# Schaltplan_Vier-Gewinnt_V2.net
KiCad netlist of a schematic drawn in EasyEDA
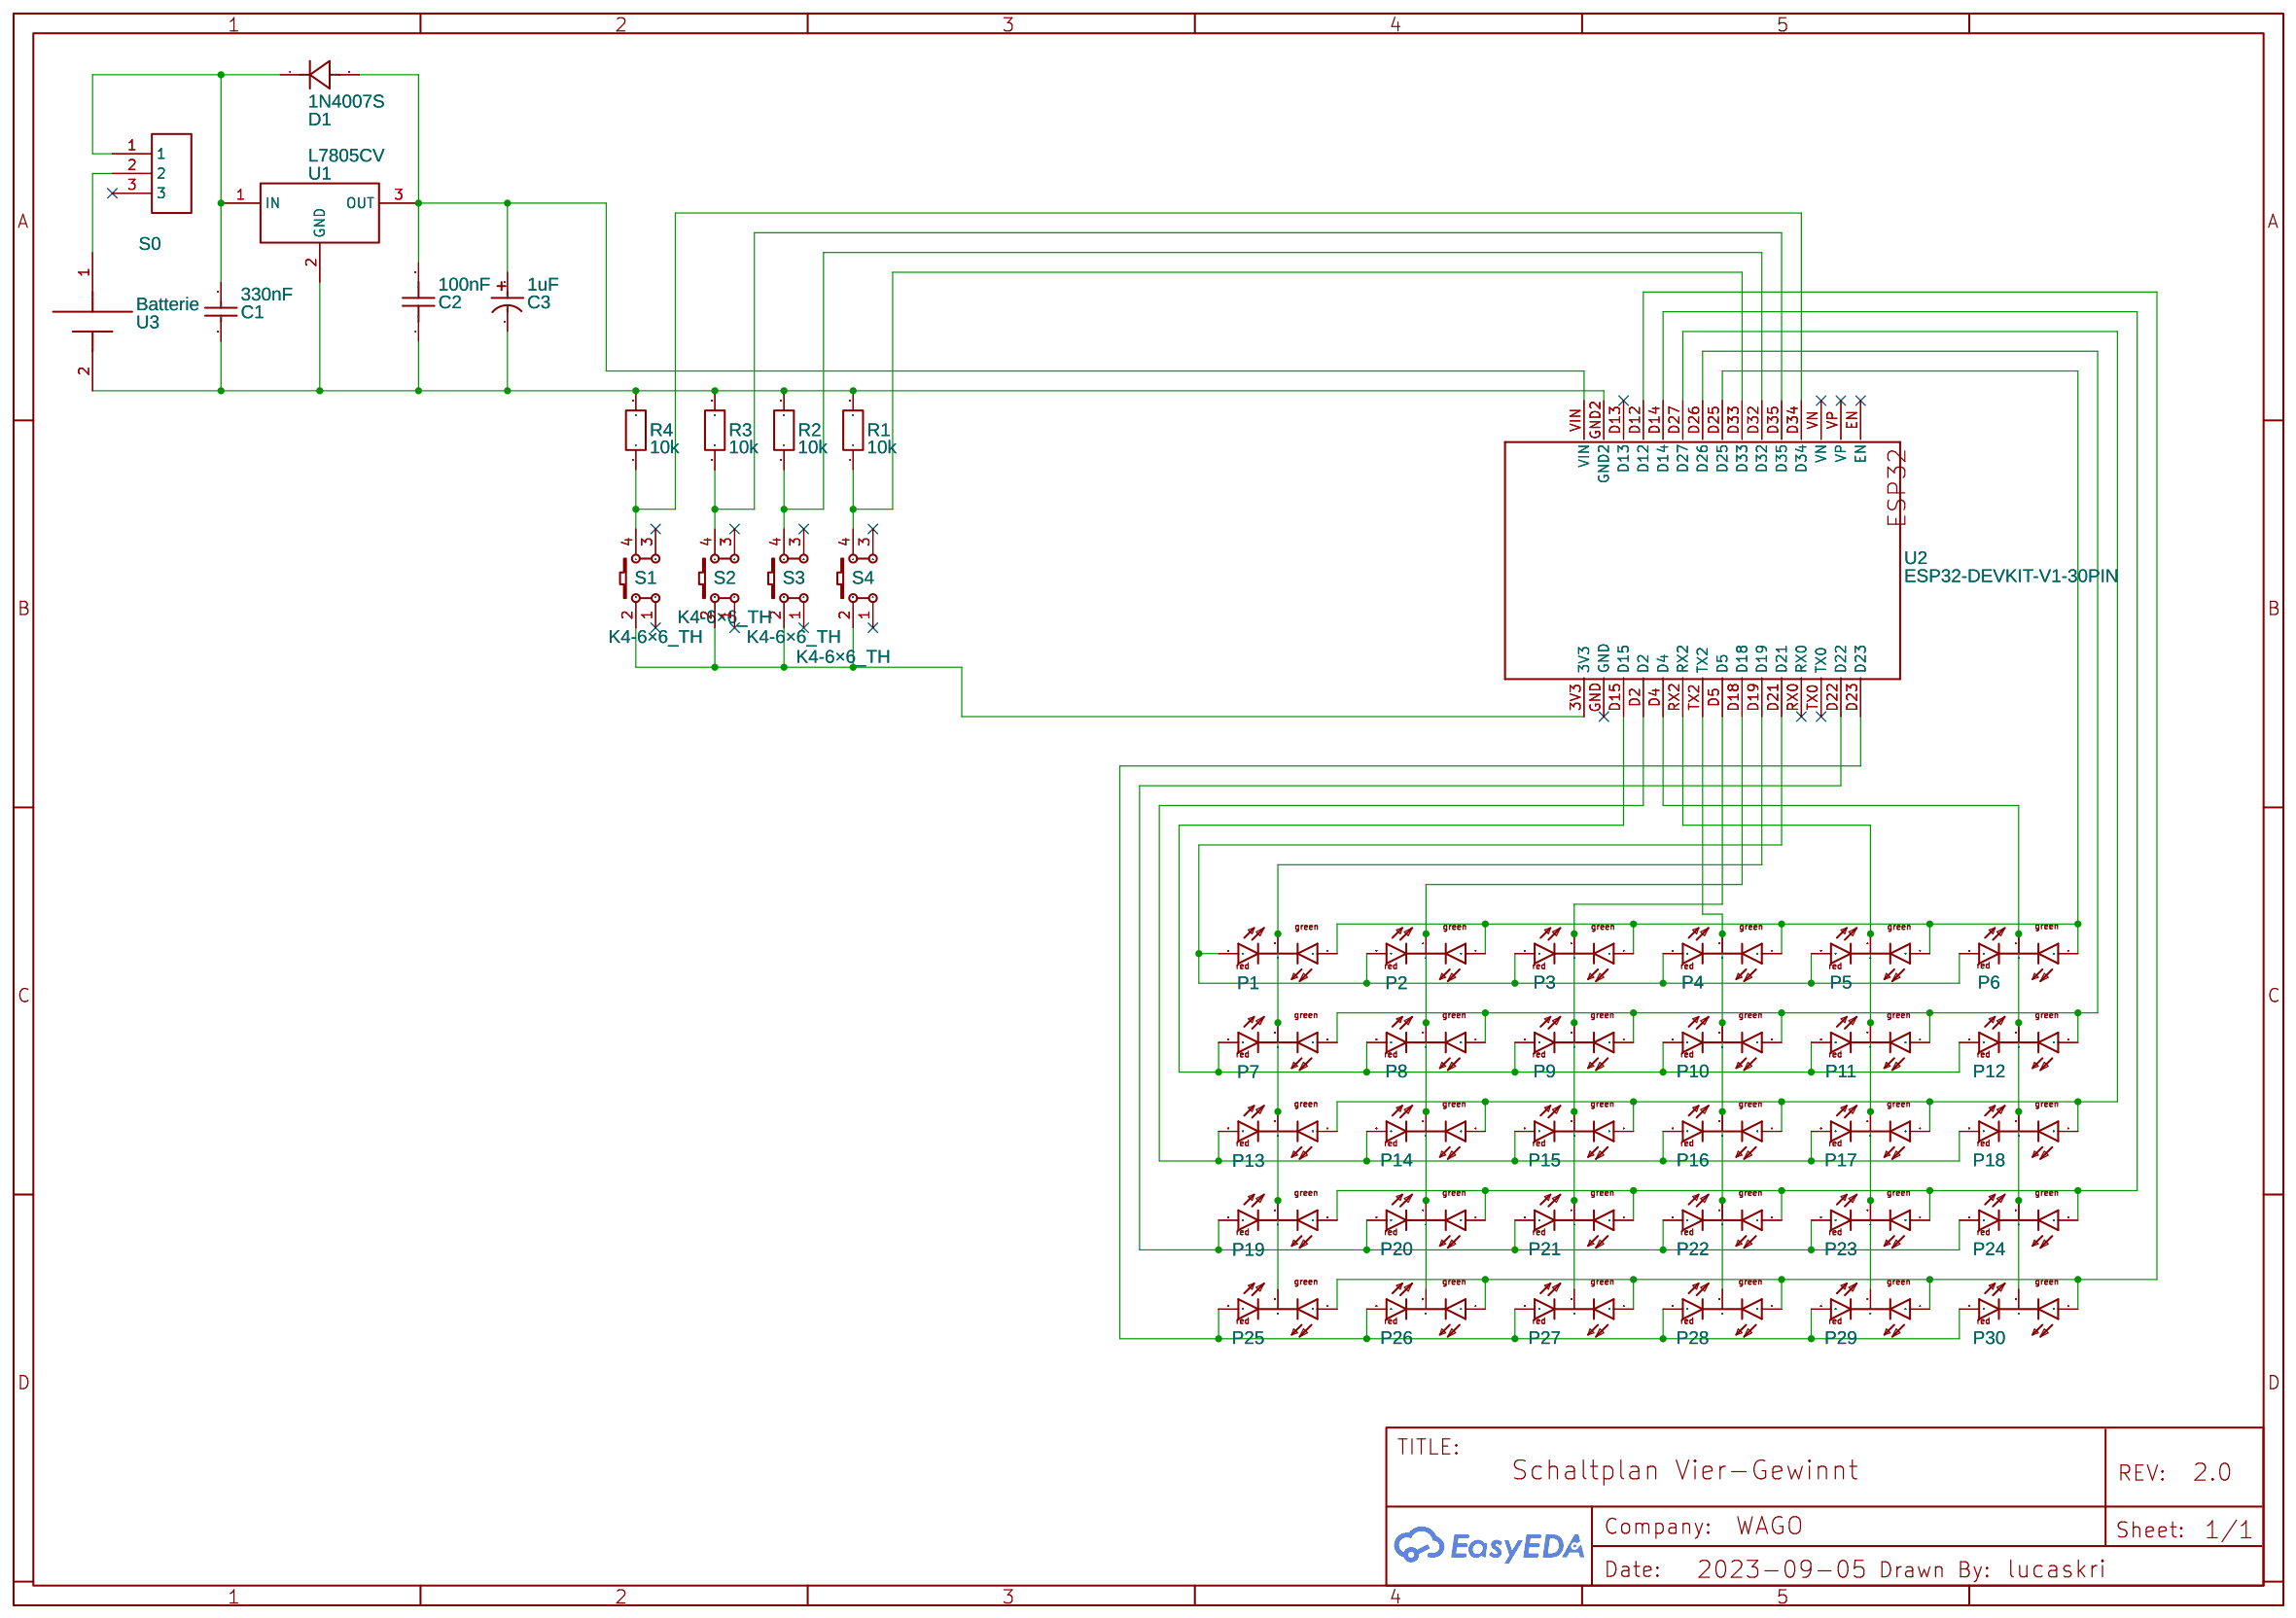
[diagram p0: schematic sheet]

(export (version "E")
  (design (tool "Eeschema 10.0.6"))
  (components
    (comp (ref "C1")
      (value "330nF")
      (fields (field (name "Manufacturer Part") "CT4-1206Y334M500PF3") (field (name "Manufacturer") "FH(风华)"))
      (libsource (lib "") (part "CT4-1206Y334M500PF3"))
    )
    (comp (ref "C2")
      (value "100nF")
      (fields (field (name "Manufacturer Part") "B32529C0104M289") (field (name "Manufacturer") "TDK"))
      (libsource (lib "") (part "B32529C0104M289"))
    )
    (comp (ref "C3")
      (value "1uF")
      (fields
        (field (name "Manufacturer Part") "KF105M050C05RR0VH2FP0")
        (field (name "Manufacturer") "CX(承兴)")
      )
      (libsource (lib "") (part "1uF 50V 4*5"))
    )
    (comp (ref "D1")
      (value "1N4007S")
      (fields (field (name "Manufacturer") "星海"))
      (libsource (lib "") (part "1N4007S"))
    )
    (comp (ref "P1") (value "NO") (libsource (lib "") (part "DUOLED-RG-C_1")))
    (comp (ref "P2") (value "NO") (libsource (lib "") (part "DUOLED-RG-C_1")))
    (comp (ref "P3") (value "NO") (libsource (lib "") (part "DUOLED-RG-C_1")))
    (comp (ref "P4") (value "NO") (libsource (lib "") (part "DUOLED-RG-C_1")))
    (comp (ref "P5") (value "NO") (libsource (lib "") (part "DUOLED-RG-C_1")))
    (comp (ref "P6") (value "NO") (libsource (lib "") (part "DUOLED-RG-C")))
    (comp (ref "P7") (value "NO") (libsource (lib "") (part "DUOLED-RG-C")))
    (comp (ref "P8") (value "NO") (libsource (lib "") (part "DUOLED-RG-C")))
    (comp (ref "P9") (value "NO") (libsource (lib "") (part "DUOLED-RG-C")))
    (comp (ref "P10") (value "NO") (libsource (lib "") (part "DUOLED-RG-C")))
    (comp (ref "P11") (value "NO") (libsource (lib "") (part "DUOLED-RG-C")))
    (comp (ref "P12") (value "NO") (libsource (lib "") (part "DUOLED-RG-C")))
    (comp (ref "P13") (value "NO") (libsource (lib "") (part "DUOLED-RG-C")))
    (comp (ref "P14") (value "NO") (libsource (lib "") (part "DUOLED-RG-C")))
    (comp (ref "P15") (value "NO") (libsource (lib "") (part "DUOLED-RG-C")))
    (comp (ref "P16") (value "NO") (libsource (lib "") (part "DUOLED-RG-C")))
    (comp (ref "P17") (value "NO") (libsource (lib "") (part "DUOLED-RG-C")))
    (comp (ref "P18") (value "NO") (libsource (lib "") (part "DUOLED-RG-C")))
    (comp (ref "P19") (value "NO") (libsource (lib "") (part "DUOLED-RG-C")))
    (comp (ref "P20") (value "NO") (libsource (lib "") (part "DUOLED-RG-C")))
    (comp (ref "P21") (value "NO") (libsource (lib "") (part "DUOLED-RG-C")))
    (comp (ref "P22") (value "NO") (libsource (lib "") (part "DUOLED-RG-C")))
    (comp (ref "P23") (value "NO") (libsource (lib "") (part "DUOLED-RG-C")))
    (comp (ref "P24") (value "NO") (libsource (lib "") (part "DUOLED-RG-C")))
    (comp (ref "P25") (value "NO") (libsource (lib "") (part "DUOLED-RG-C")))
    (comp (ref "P26") (value "NO") (libsource (lib "") (part "DUOLED-RG-C")))
    (comp (ref "P27") (value "NO") (libsource (lib "") (part "DUOLED-RG-C")))
    (comp (ref "P28") (value "NO") (libsource (lib "") (part "DUOLED-RG-C")))
    (comp (ref "P29") (value "NO") (libsource (lib "") (part "DUOLED-RG-C")))
    (comp (ref "P30") (value "NO") (libsource (lib "") (part "DUOLED-RG-C")))
    (comp (ref "R1") (value "10k") (libsource (lib "") (part "R_AXIAL-0.3_EU")))
    (comp (ref "R2") (value "10k") (libsource (lib "") (part "R_AXIAL-0.3_EU")))
    (comp (ref "R3") (value "10k") (libsource (lib "") (part "R_AXIAL-0.3_EU")))
    (comp (ref "R4") (value "10k") (libsource (lib "") (part "R_AXIAL-0.3_EU")))
    (comp (ref "S0") (value "NO") (libsource (lib "") (part "CSS-1201")))
    (comp (ref "S1")
      (value "K4-6×6_TH")
      (fields (field (name "Manufacturer Part") "K2-1102DP-E4SW-04") (field (name "Manufacturer") "韩国韩荣"))
      (libsource (lib "") (part "K4-6×6_TH"))
    )
    (comp (ref "S2")
      (value "K4-6×6_TH")
      (fields (field (name "Manufacturer Part") "K2-1102DP-E4SW-04") (field (name "Manufacturer") "韩国韩荣"))
      (libsource (lib "") (part "K4-6×6_TH"))
    )
    (comp (ref "S3")
      (value "K4-6×6_TH")
      (fields (field (name "Manufacturer Part") "K2-1102DP-E4SW-04") (field (name "Manufacturer") "韩国韩荣"))
      (libsource (lib "") (part "K4-6×6_TH"))
    )
    (comp (ref "S4")
      (value "K4-6×6_TH")
      (fields (field (name "Manufacturer Part") "K2-1102DP-E4SW-04") (field (name "Manufacturer") "韩国韩荣"))
      (libsource (lib "") (part "K4-6×6_TH"))
    )
    (comp (ref "U1")
      (value "L7805CV")
      (fields (field (name "Manufacturer") "STMicroelectronics"))
      (libsource (lib "") (part "L7805CV"))
    )
    (comp (ref "U2") (value "ESP32-DEVKIT-V1-30PIN") (libsource (lib "") (part "ESP32-DEVKIT-V1-30PIN")))
    (comp (ref "U3") (value "Batterie") (libsource (lib "") (part "Batterie")))
  )
  (nets
    (net (code "1") (name "Net-(D1-A)") (class "Default")
      (node (ref "C2") (pin "2") (pinfunction "2_2") (pintype "unspecified"))
      (node (ref "C3") (pin "1") (pinfunction "1_1") (pintype "input"))
      (node (ref "D1") (pin "2") (pinfunction "A_2") (pintype "unspecified"))
      (node (ref "U1") (pin "3") (pinfunction "OUT_3") (pintype "unspecified"))
      (node (ref "U2") (pin "VIN") (pinfunction "VIN_VIN") (pintype "unspecified"))
    )
    (net (code "2") (name "Net-(D1-K)") (class "Default")
      (node (ref "C1") (pin "2") (pinfunction "2_2") (pintype "input"))
      (node (ref "D1") (pin "1") (pinfunction "K_1") (pintype "unspecified"))
      (node (ref "S0") (pin "1") (pinfunction "1_1") (pintype "unspecified"))
      (node (ref "U1") (pin "1") (pinfunction "IN_1") (pintype "unspecified"))
    )
    (net (code "3") (name "Net-(P1-AG)") (class "Default")
      (node (ref "P1") (pin "AX") (pinfunction "AG_AX") (pintype "bidirectional"))
      (node (ref "P2") (pin "AX") (pinfunction "AG_AX") (pintype "bidirectional"))
      (node (ref "P3") (pin "AX") (pinfunction "AG_AX") (pintype "bidirectional"))
      (node (ref "P4") (pin "AX") (pinfunction "AG_AX") (pintype "bidirectional"))
      (node (ref "P5") (pin "AX") (pinfunction "AG_AX") (pintype "bidirectional"))
      (node (ref "P6") (pin "AX") (pinfunction "AG_AX") (pintype "bidirectional"))
      (node (ref "U2") (pin "D25") (pinfunction "D25_D25") (pintype "unspecified"))
    )
    (net (code "4") (name "Net-(P1-PadAR)") (class "Default")
      (node (ref "P1") (pin "AR") (pinfunction "AR_AR") (pintype "bidirectional"))
      (node (ref "P2") (pin "AR") (pinfunction "AR_AR") (pintype "bidirectional"))
      (node (ref "P3") (pin "AR") (pinfunction "AR_AR") (pintype "bidirectional"))
      (node (ref "P4") (pin "AR") (pinfunction "AR_AR") (pintype "bidirectional"))
      (node (ref "P5") (pin "AR") (pinfunction "AR_AR") (pintype "bidirectional"))
      (node (ref "P6") (pin "AR") (pinfunction "AR_AR") (pintype "bidirectional"))
      (node (ref "U2") (pin "D21") (pinfunction "D21_D21") (pintype "unspecified"))
    )
    (net (code "5") (name "Net-(P1-PadC)") (class "Default")
      (node (ref "P1") (pin "C") (pinfunction "C_C") (pintype "bidirectional"))
      (node (ref "P13") (pin "C") (pinfunction "C_C") (pintype "bidirectional"))
      (node (ref "P19") (pin "C") (pinfunction "C_C") (pintype "bidirectional"))
      (node (ref "P25") (pin "C") (pinfunction "C_C") (pintype "bidirectional"))
      (node (ref "P7") (pin "C") (pinfunction "C_C") (pintype "bidirectional"))
      (node (ref "U2") (pin "D19") (pinfunction "D19_D19") (pintype "unspecified"))
    )
    (net (code "6") (name "Net-(P10-AG)") (class "Default")
      (node (ref "P10") (pin "AX") (pinfunction "AG_AX") (pintype "bidirectional"))
      (node (ref "P11") (pin "AX") (pinfunction "AG_AX") (pintype "bidirectional"))
      (node (ref "P12") (pin "AX") (pinfunction "AG_AX") (pintype "bidirectional"))
      (node (ref "P7") (pin "AX") (pinfunction "AG_AX") (pintype "bidirectional"))
      (node (ref "P8") (pin "AX") (pinfunction "AG_AX") (pintype "bidirectional"))
      (node (ref "P9") (pin "AX") (pinfunction "AG_AX") (pintype "bidirectional"))
      (node (ref "U2") (pin "D26") (pinfunction "D26_D26") (pintype "unspecified"))
    )
    (net (code "7") (name "Net-(P10-PadAR)") (class "Default")
      (node (ref "P10") (pin "AR") (pinfunction "AR_AR") (pintype "bidirectional"))
      (node (ref "P11") (pin "AR") (pinfunction "AR_AR") (pintype "bidirectional"))
      (node (ref "P12") (pin "AR") (pinfunction "AR_AR") (pintype "bidirectional"))
      (node (ref "P7") (pin "AR") (pinfunction "AR_AR") (pintype "bidirectional"))
      (node (ref "P8") (pin "AR") (pinfunction "AR_AR") (pintype "bidirectional"))
      (node (ref "P9") (pin "AR") (pinfunction "AR_AR") (pintype "bidirectional"))
      (node (ref "U2") (pin "D15") (pinfunction "D15_D15") (pintype "unspecified"))
    )
    (net (code "8") (name "Net-(P10-PadC)") (class "Default")
      (node (ref "P10") (pin "C") (pinfunction "C_C") (pintype "bidirectional"))
      (node (ref "P16") (pin "C") (pinfunction "C_C") (pintype "bidirectional"))
      (node (ref "P22") (pin "C") (pinfunction "C_C") (pintype "bidirectional"))
      (node (ref "P28") (pin "C") (pinfunction "C_C") (pintype "bidirectional"))
      (node (ref "P4") (pin "C") (pinfunction "C_C") (pintype "bidirectional"))
      (node (ref "U2") (pin "TX2") (pinfunction "TX2_TX2") (pintype "unspecified"))
    )
    (net (code "9") (name "Net-(P11-PadC)") (class "Default")
      (node (ref "P11") (pin "C") (pinfunction "C_C") (pintype "bidirectional"))
      (node (ref "P17") (pin "C") (pinfunction "C_C") (pintype "bidirectional"))
      (node (ref "P23") (pin "C") (pinfunction "C_C") (pintype "bidirectional"))
      (node (ref "P29") (pin "C") (pinfunction "C_C") (pintype "bidirectional"))
      (node (ref "P5") (pin "C") (pinfunction "C_C") (pintype "bidirectional"))
      (node (ref "U2") (pin "RX2") (pinfunction "RX2_RX2") (pintype "unspecified"))
    )
    (net (code "10") (name "Net-(P12-PadC)") (class "Default")
      (node (ref "P12") (pin "C") (pinfunction "C_C") (pintype "bidirectional"))
      (node (ref "P18") (pin "C") (pinfunction "C_C") (pintype "bidirectional"))
      (node (ref "P24") (pin "C") (pinfunction "C_C") (pintype "bidirectional"))
      (node (ref "P30") (pin "C") (pinfunction "C_C") (pintype "bidirectional"))
      (node (ref "P6") (pin "C") (pinfunction "C_C") (pintype "bidirectional"))
      (node (ref "U2") (pin "D4") (pinfunction "D4_D4") (pintype "unspecified"))
    )
    (net (code "11") (name "Net-(P13-AG)") (class "Default")
      (node (ref "P13") (pin "AX") (pinfunction "AG_AX") (pintype "bidirectional"))
      (node (ref "P14") (pin "AX") (pinfunction "AG_AX") (pintype "bidirectional"))
      (node (ref "P15") (pin "AX") (pinfunction "AG_AX") (pintype "bidirectional"))
      (node (ref "P16") (pin "AX") (pinfunction "AG_AX") (pintype "bidirectional"))
      (node (ref "P17") (pin "AX") (pinfunction "AG_AX") (pintype "bidirectional"))
      (node (ref "P18") (pin "AX") (pinfunction "AG_AX") (pintype "bidirectional"))
      (node (ref "U2") (pin "D27") (pinfunction "D27_D27") (pintype "unspecified"))
    )
    (net (code "12") (name "Net-(P13-PadAR)") (class "Default")
      (node (ref "P13") (pin "AR") (pinfunction "AR_AR") (pintype "bidirectional"))
      (node (ref "P14") (pin "AR") (pinfunction "AR_AR") (pintype "bidirectional"))
      (node (ref "P15") (pin "AR") (pinfunction "AR_AR") (pintype "bidirectional"))
      (node (ref "P16") (pin "AR") (pinfunction "AR_AR") (pintype "bidirectional"))
      (node (ref "P17") (pin "AR") (pinfunction "AR_AR") (pintype "bidirectional"))
      (node (ref "P18") (pin "AR") (pinfunction "AR_AR") (pintype "bidirectional"))
      (node (ref "U2") (pin "D2") (pinfunction "D2_D2") (pintype "unspecified"))
    )
    (net (code "13") (name "Net-(P14-PadC)") (class "Default")
      (node (ref "P14") (pin "C") (pinfunction "C_C") (pintype "bidirectional"))
      (node (ref "P2") (pin "C") (pinfunction "C_C") (pintype "bidirectional"))
      (node (ref "P20") (pin "C") (pinfunction "C_C") (pintype "bidirectional"))
      (node (ref "P26") (pin "C") (pinfunction "C_C") (pintype "bidirectional"))
      (node (ref "P8") (pin "C") (pinfunction "C_C") (pintype "bidirectional"))
      (node (ref "U2") (pin "D18") (pinfunction "D18_D18") (pintype "unspecified"))
    )
    (net (code "14") (name "Net-(P15-PadC)") (class "Default")
      (node (ref "P15") (pin "C") (pinfunction "C_C") (pintype "bidirectional"))
      (node (ref "P21") (pin "C") (pinfunction "C_C") (pintype "bidirectional"))
      (node (ref "P27") (pin "C") (pinfunction "C_C") (pintype "bidirectional"))
      (node (ref "P3") (pin "C") (pinfunction "C_C") (pintype "bidirectional"))
      (node (ref "P9") (pin "C") (pinfunction "C_C") (pintype "bidirectional"))
      (node (ref "U2") (pin "D5") (pinfunction "D5_D5") (pintype "unspecified"))
    )
    (net (code "15") (name "Net-(P19-AG)") (class "Default")
      (node (ref "P19") (pin "AX") (pinfunction "AG_AX") (pintype "bidirectional"))
      (node (ref "P20") (pin "AX") (pinfunction "AG_AX") (pintype "bidirectional"))
      (node (ref "P21") (pin "AX") (pinfunction "AG_AX") (pintype "bidirectional"))
      (node (ref "P22") (pin "AX") (pinfunction "AG_AX") (pintype "bidirectional"))
      (node (ref "P23") (pin "AX") (pinfunction "AG_AX") (pintype "bidirectional"))
      (node (ref "P24") (pin "AX") (pinfunction "AG_AX") (pintype "bidirectional"))
      (node (ref "U2") (pin "D14") (pinfunction "D14_D14") (pintype "unspecified"))
    )
    (net (code "16") (name "Net-(P19-PadAR)") (class "Default")
      (node (ref "P19") (pin "AR") (pinfunction "AR_AR") (pintype "bidirectional"))
      (node (ref "P20") (pin "AR") (pinfunction "AR_AR") (pintype "bidirectional"))
      (node (ref "P21") (pin "AR") (pinfunction "AR_AR") (pintype "bidirectional"))
      (node (ref "P22") (pin "AR") (pinfunction "AR_AR") (pintype "bidirectional"))
      (node (ref "P23") (pin "AR") (pinfunction "AR_AR") (pintype "bidirectional"))
      (node (ref "P24") (pin "AR") (pinfunction "AR_AR") (pintype "bidirectional"))
      (node (ref "U2") (pin "D22") (pinfunction "D22_D22") (pintype "unspecified"))
    )
    (net (code "17") (name "Net-(P25-AG)") (class "Default")
      (node (ref "P25") (pin "AX") (pinfunction "AG_AX") (pintype "bidirectional"))
      (node (ref "P26") (pin "AX") (pinfunction "AG_AX") (pintype "bidirectional"))
      (node (ref "P27") (pin "AX") (pinfunction "AG_AX") (pintype "bidirectional"))
      (node (ref "P28") (pin "AX") (pinfunction "AG_AX") (pintype "bidirectional"))
      (node (ref "P29") (pin "AX") (pinfunction "AG_AX") (pintype "bidirectional"))
      (node (ref "P30") (pin "AX") (pinfunction "AG_AX") (pintype "bidirectional"))
      (node (ref "U2") (pin "D12") (pinfunction "D12_D12") (pintype "unspecified"))
    )
    (net (code "18") (name "Net-(P25-PadAR)") (class "Default")
      (node (ref "P25") (pin "AR") (pinfunction "AR_AR") (pintype "bidirectional"))
      (node (ref "P26") (pin "AR") (pinfunction "AR_AR") (pintype "bidirectional"))
      (node (ref "P27") (pin "AR") (pinfunction "AR_AR") (pintype "bidirectional"))
      (node (ref "P28") (pin "AR") (pinfunction "AR_AR") (pintype "bidirectional"))
      (node (ref "P29") (pin "AR") (pinfunction "AR_AR") (pintype "bidirectional"))
      (node (ref "P30") (pin "AR") (pinfunction "AR_AR") (pintype "bidirectional"))
      (node (ref "U2") (pin "D23") (pinfunction "D23_D23") (pintype "unspecified"))
    )
    (net (code "19") (name "Net-(R1-Pad1)") (class "Default")
      (node (ref "R1") (pin "1") (pinfunction "1_1") (pintype "unspecified"))
      (node (ref "S4") (pin "4") (pinfunction "4_4") (pintype "unspecified"))
      (node (ref "U2") (pin "D33") (pinfunction "D33_D33") (pintype "unspecified"))
    )
    (net (code "20") (name "Net-(R2-Pad1)") (class "Default")
      (node (ref "R2") (pin "1") (pinfunction "1_1") (pintype "unspecified"))
      (node (ref "S3") (pin "4") (pinfunction "4_4") (pintype "unspecified"))
      (node (ref "U2") (pin "D32") (pinfunction "D32_D32") (pintype "unspecified"))
    )
    (net (code "21") (name "Net-(R3-Pad1)") (class "Default")
      (node (ref "R3") (pin "1") (pinfunction "1_1") (pintype "unspecified"))
      (node (ref "S2") (pin "4") (pinfunction "4_4") (pintype "unspecified"))
      (node (ref "U2") (pin "D35") (pinfunction "D35_D35") (pintype "unspecified"))
    )
    (net (code "22") (name "Net-(R4-Pad1)") (class "Default")
      (node (ref "R4") (pin "1") (pinfunction "1_1") (pintype "unspecified"))
      (node (ref "S1") (pin "4") (pinfunction "4_4") (pintype "unspecified"))
      (node (ref "U2") (pin "D34") (pinfunction "D34_D34") (pintype "unspecified"))
    )
    (net (code "23") (name "Net-(S1-Pad2)") (class "Default")
      (node (ref "S1") (pin "2") (pinfunction "2_2") (pintype "unspecified"))
      (node (ref "S2") (pin "2") (pinfunction "2_2") (pintype "unspecified"))
      (node (ref "S3") (pin "2") (pinfunction "2_2") (pintype "unspecified"))
      (node (ref "S4") (pin "2") (pinfunction "2_2") (pintype "unspecified"))
      (node (ref "U2") (pin "3V3") (pinfunction "3V3_3V3") (pintype "unspecified"))
    )
    (net (code "24") (name "Net-(U1-GND)") (class "Default")
      (node (ref "C1") (pin "1") (pinfunction "1_1") (pintype "input"))
      (node (ref "C2") (pin "1") (pinfunction "1_1") (pintype "unspecified"))
      (node (ref "C3") (pin "2") (pinfunction "2_2") (pintype "input"))
      (node (ref "R1") (pin "2") (pinfunction "2_2") (pintype "unspecified"))
      (node (ref "R2") (pin "2") (pinfunction "2_2") (pintype "unspecified"))
      (node (ref "R3") (pin "2") (pinfunction "2_2") (pintype "unspecified"))
      (node (ref "R4") (pin "2") (pinfunction "2_2") (pintype "unspecified"))
      (node (ref "U1") (pin "2") (pinfunction "GND_2") (pintype "unspecified"))
      (node (ref "U2") (pin "GND2") (pinfunction "GND2_GND2") (pintype "unspecified"))
      (node (ref "U3") (pin "2") (pinfunction "-_2") (pintype "unspecified"))
    )
    (net (code "25") (name "Net-(U3-+)") (class "Default")
      (node (ref "S0") (pin "2") (pinfunction "2_2") (pintype "unspecified"))
      (node (ref "U3") (pin "1") (pinfunction "+_1") (pintype "unspecified"))
    )
    (net (code "26") (name "unconnected-(S0-Pad3)") (class "Default")
      (node (ref "S0") (pin "3") (pinfunction "3_3") (pintype "unspecified+no_connect"))
    )
    (net (code "27") (name "unconnected-(S1-Pad1)") (class "Default")
      (node (ref "S1") (pin "1") (pinfunction "1_1") (pintype "unspecified+no_connect"))
    )
    (net (code "28") (name "unconnected-(S1-Pad3)") (class "Default")
      (node (ref "S1") (pin "3") (pinfunction "3_3") (pintype "unspecified+no_connect"))
    )
    (net (code "29") (name "unconnected-(S2-Pad1)") (class "Default")
      (node (ref "S2") (pin "1") (pinfunction "1_1") (pintype "unspecified+no_connect"))
    )
    (net (code "30") (name "unconnected-(S2-Pad3)") (class "Default")
      (node (ref "S2") (pin "3") (pinfunction "3_3") (pintype "unspecified+no_connect"))
    )
    (net (code "31") (name "unconnected-(S3-Pad1)") (class "Default")
      (node (ref "S3") (pin "1") (pinfunction "1_1") (pintype "unspecified+no_connect"))
    )
    (net (code "32") (name "unconnected-(S3-Pad3)") (class "Default")
      (node (ref "S3") (pin "3") (pinfunction "3_3") (pintype "unspecified+no_connect"))
    )
    (net (code "33") (name "unconnected-(S4-Pad1)") (class "Default")
      (node (ref "S4") (pin "1") (pinfunction "1_1") (pintype "unspecified+no_connect"))
    )
    (net (code "34") (name "unconnected-(S4-Pad3)") (class "Default")
      (node (ref "S4") (pin "3") (pinfunction "3_3") (pintype "unspecified+no_connect"))
    )
    (net (code "35") (name "unconnected-(U2-PadD13)") (class "Default")
      (node (ref "U2") (pin "D13") (pinfunction "D13_D13") (pintype "unspecified+no_connect"))
    )
    (net (code "36") (name "unconnected-(U2-PadEN)") (class "Default")
      (node (ref "U2") (pin "EN") (pinfunction "EN_EN") (pintype "unspecified+no_connect"))
    )
    (net (code "37") (name "unconnected-(U2-PadGND)") (class "Default")
      (node (ref "U2") (pin "GND") (pinfunction "GND_GND") (pintype "unspecified+no_connect"))
    )
    (net (code "38") (name "unconnected-(U2-PadRX0)") (class "Default")
      (node (ref "U2") (pin "RX0") (pinfunction "RX0_RX0") (pintype "unspecified+no_connect"))
    )
    (net (code "39") (name "unconnected-(U2-PadTX0)") (class "Default")
      (node (ref "U2") (pin "TX0") (pinfunction "TX0_TX0") (pintype "unspecified+no_connect"))
    )
    (net (code "40") (name "unconnected-(U2-PadVN)") (class "Default")
      (node (ref "U2") (pin "VN") (pinfunction "VN_VN") (pintype "unspecified+no_connect"))
    )
    (net (code "41") (name "unconnected-(U2-PadVP)") (class "Default")
      (node (ref "U2") (pin "VP") (pinfunction "VP_VP") (pintype "unspecified+no_connect"))
    )
  )
)
